# M239X.net
KiCad netlist of a schematic drawn in EAGLE
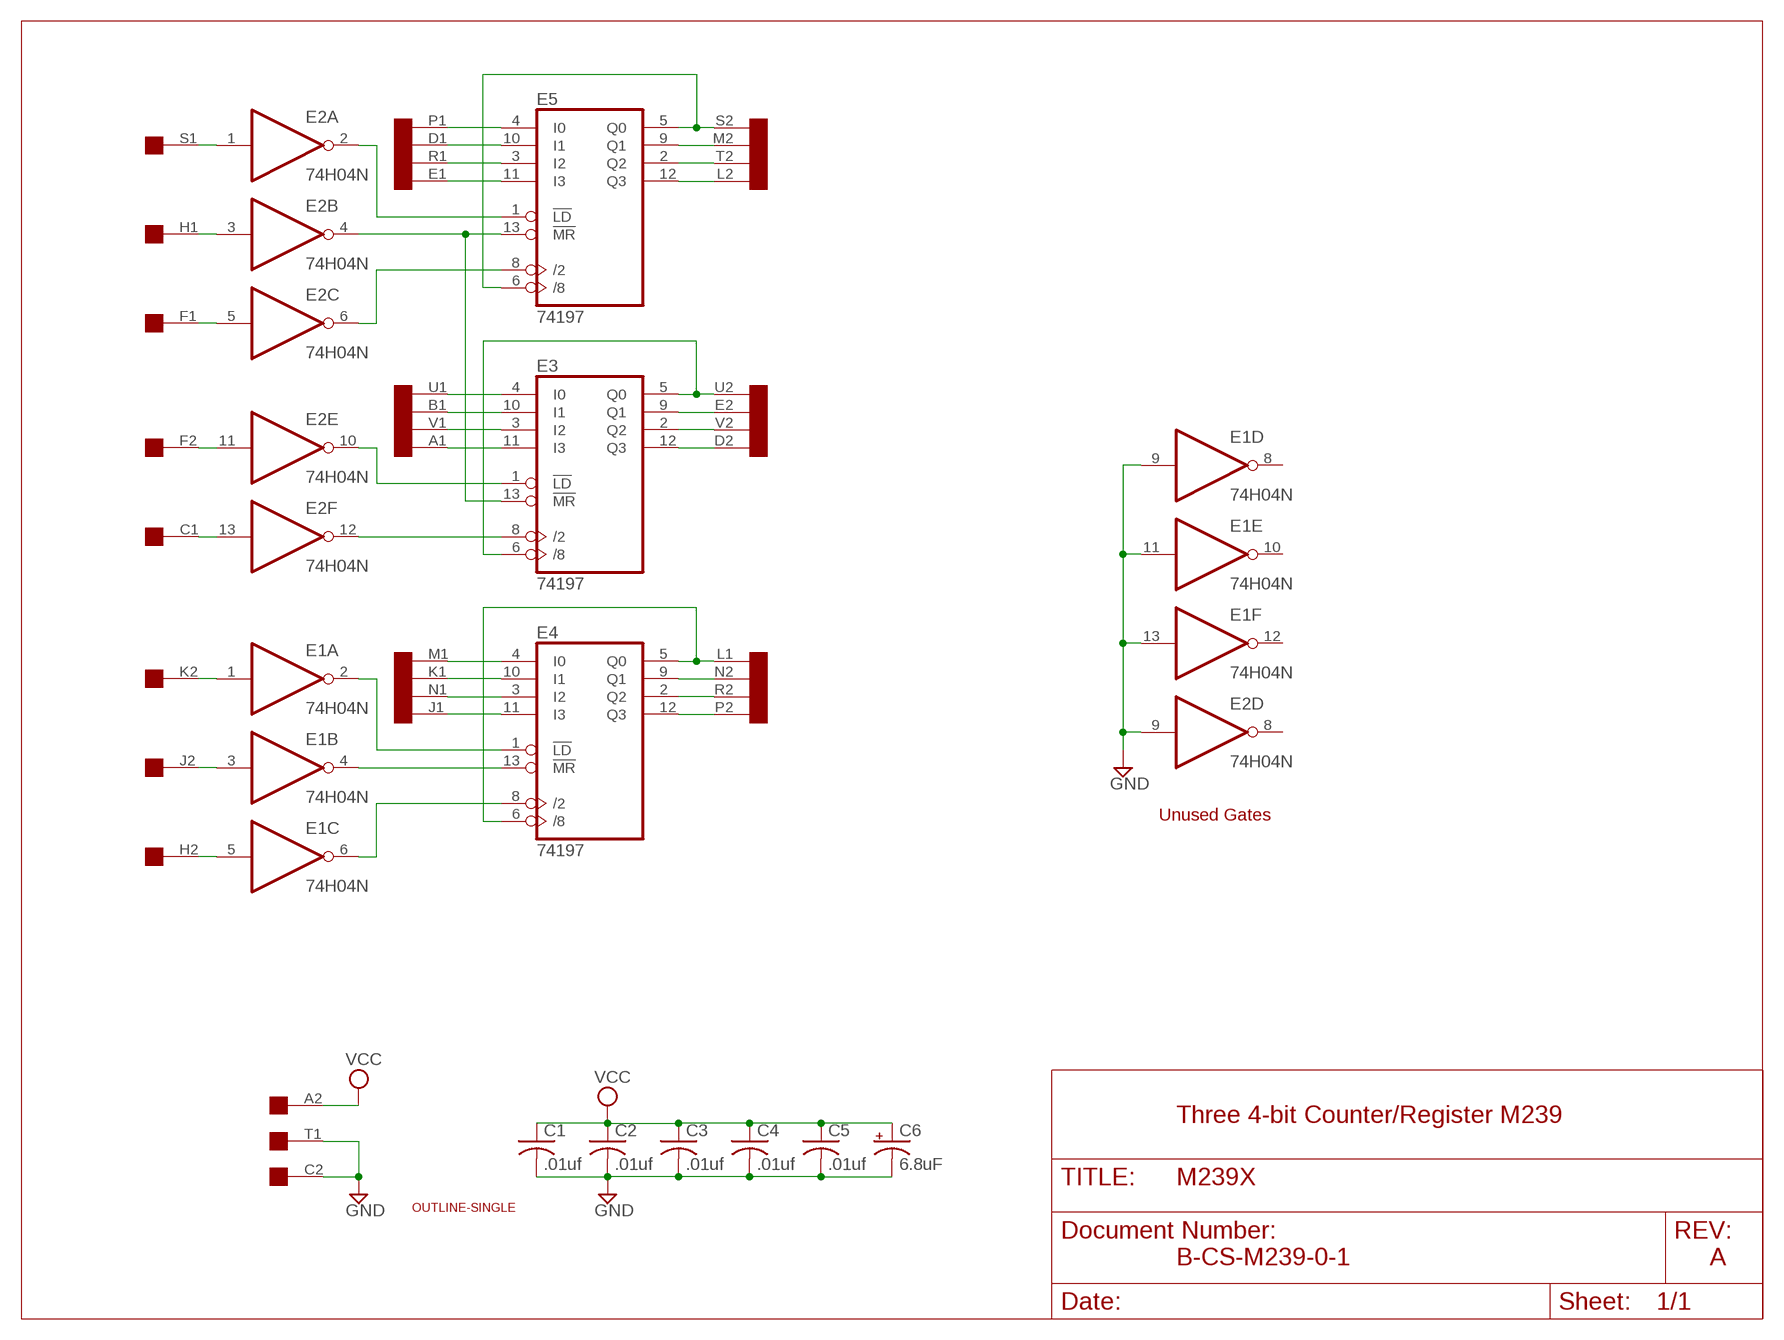
[diagram p0: schematic, sheet 1]

(export (version "E")
  (design (tool "Eeschema 10.0.6"))
  (components
    (comp (ref "C1")
      (value ".01uf")
      (footprint "eagle-import:C050-025X075")
      (libsource (lib "eagle-import") (part "C-US050-025X075"))
    )
    (comp (ref "C2")
      (value ".01uf")
      (footprint "eagle-import:C050-025X075")
      (libsource (lib "eagle-import") (part "C-US050-025X075"))
    )
    (comp (ref "C3")
      (value ".01uf")
      (footprint "eagle-import:C050-025X075")
      (libsource (lib "eagle-import") (part "C-US050-025X075"))
    )
    (comp (ref "C4")
      (value ".01uf")
      (footprint "eagle-import:C050-025X075")
      (libsource (lib "eagle-import") (part "C-US050-025X075"))
    )
    (comp (ref "C5")
      (value ".01uf")
      (footprint "eagle-import:C050-025X075")
      (libsource (lib "eagle-import") (part "C-US050-025X075"))
    )
    (comp (ref "C6")
      (value "6.8uF")
      (footprint "eagle-import:E22-6")
      (libsource (lib "eagle-import") (part "CPOL-USE22-6AXIAL"))
    )
    (comp (ref "E1")
      (value "74H04N")
      (footprint "eagle-import:DIL14")
      (libsource (lib "eagle-import") (part "7404N"))
    )
    (comp (ref "E2")
      (value "74H04N")
      (footprint "eagle-import:DIL14")
      (libsource (lib "eagle-import") (part "7404N"))
    )
    (comp (ref "E3")
      (value "74197")
      (footprint "eagle-import:DIL14")
      (libsource (lib "eagle-import") (part "74LS197"))
    )
    (comp (ref "E4")
      (value "74197")
      (footprint "eagle-import:DIL14")
      (libsource (lib "eagle-import") (part "74LS197"))
    )
    (comp (ref "E5")
      (value "74197")
      (footprint "eagle-import:DIL14")
      (libsource (lib "eagle-import") (part "74LS197"))
    )
    (comp (ref "U$1")
      (value "OUTLINE-SINGLE")
      (footprint "eagle-import:SINGLE")
      (libsource (lib "eagle-import") (part "OUTLINE-SINGLE"))
    )
    (comp (ref "U$4")
      (value "SINGLE")
      (footprint "eagle-import:EDGE-CON2")
      (libsource (lib "eagle-import") (part "SINGLE"))
    )
  )
  (nets
    (net (code "1") (name "GND") (class "Default")
      (node (ref "C1") (pin "2") (pinfunction "2_2") (pintype "passive"))
      (node (ref "C2") (pin "2") (pinfunction "2_2") (pintype "passive"))
      (node (ref "C3") (pin "2") (pinfunction "2_2") (pintype "passive"))
      (node (ref "C4") (pin "2") (pinfunction "2_2") (pintype "passive"))
      (node (ref "C5") (pin "2") (pinfunction "2_2") (pintype "passive"))
      (node (ref "C6") (pin "-") (pinfunction "-_-") (pintype "passive"))
      (node (ref "E1") (pin "11") (pinfunction "I_11") (pintype "input"))
      (node (ref "E1") (pin "13") (pinfunction "I_13") (pintype "input"))
      (node (ref "E1") (pin "9") (pinfunction "I_9") (pintype "input"))
      (node (ref "E2") (pin "9") (pinfunction "I_9") (pintype "input"))
      (node (ref "U$4") (pin "C2") (pinfunction "1_C2") (pintype "bidirectional"))
      (node (ref "U$4") (pin "T1") (pinfunction "1_T1") (pintype "bidirectional"))
    )
    (net (code "2") (name "Net-(E1A-I)") (class "Default")
      (node (ref "E1") (pin "1") (pinfunction "I_1") (pintype "input"))
      (node (ref "U$4") (pin "K2") (pinfunction "1_K2") (pintype "bidirectional"))
    )
    (net (code "3") (name "Net-(E1A-O)") (class "Default")
      (node (ref "E1") (pin "2") (pinfunction "O_2") (pintype "output"))
      (node (ref "E4") (pin "1") (pinfunction "~{LD}_1") (pintype "input"))
    )
    (net (code "4") (name "Net-(E1B-I)") (class "Default")
      (node (ref "E1") (pin "3") (pinfunction "I_3") (pintype "input"))
      (node (ref "U$4") (pin "J2") (pinfunction "1_J2") (pintype "bidirectional"))
    )
    (net (code "5") (name "Net-(E1B-O)") (class "Default")
      (node (ref "E1") (pin "4") (pinfunction "O_4") (pintype "output"))
      (node (ref "E4") (pin "13") (pinfunction "~{MR}_13") (pintype "input"))
    )
    (net (code "6") (name "Net-(E1C-I)") (class "Default")
      (node (ref "E1") (pin "5") (pinfunction "I_5") (pintype "input"))
      (node (ref "U$4") (pin "H2") (pinfunction "1_H2") (pintype "bidirectional"))
    )
    (net (code "7") (name "Net-(E1C-O)") (class "Default")
      (node (ref "E1") (pin "6") (pinfunction "O_6") (pintype "output"))
      (node (ref "E4") (pin "8") (pinfunction "/2_8") (pintype "bidirectional"))
    )
    (net (code "8") (name "Net-(E2A-I)") (class "Default")
      (node (ref "E2") (pin "1") (pinfunction "I_1") (pintype "input"))
      (node (ref "U$4") (pin "S1") (pinfunction "1_S1") (pintype "bidirectional"))
    )
    (net (code "9") (name "Net-(E2A-O)") (class "Default")
      (node (ref "E2") (pin "2") (pinfunction "O_2") (pintype "output"))
      (node (ref "E5") (pin "1") (pinfunction "~{LD}_1") (pintype "input"))
    )
    (net (code "10") (name "Net-(E2B-I)") (class "Default")
      (node (ref "E2") (pin "3") (pinfunction "I_3") (pintype "input"))
      (node (ref "U$4") (pin "H1") (pinfunction "1_H1") (pintype "bidirectional"))
    )
    (net (code "11") (name "Net-(E2B-O)") (class "Default")
      (node (ref "E2") (pin "4") (pinfunction "O_4") (pintype "output"))
      (node (ref "E3") (pin "13") (pinfunction "~{MR}_13") (pintype "input"))
      (node (ref "E5") (pin "13") (pinfunction "~{MR}_13") (pintype "input"))
    )
    (net (code "12") (name "Net-(E2C-I)") (class "Default")
      (node (ref "E2") (pin "5") (pinfunction "I_5") (pintype "input"))
      (node (ref "U$4") (pin "F1") (pinfunction "1_F1") (pintype "bidirectional"))
    )
    (net (code "13") (name "Net-(E2C-O)") (class "Default")
      (node (ref "E2") (pin "6") (pinfunction "O_6") (pintype "output"))
      (node (ref "E5") (pin "8") (pinfunction "/2_8") (pintype "bidirectional"))
    )
    (net (code "14") (name "Net-(E2E-I)") (class "Default")
      (node (ref "E2") (pin "11") (pinfunction "I_11") (pintype "input"))
      (node (ref "U$4") (pin "F2") (pinfunction "1_F2") (pintype "bidirectional"))
    )
    (net (code "15") (name "Net-(E2E-O)") (class "Default")
      (node (ref "E2") (pin "10") (pinfunction "O_10") (pintype "output"))
      (node (ref "E3") (pin "1") (pinfunction "~{LD}_1") (pintype "input"))
    )
    (net (code "16") (name "Net-(E2F-I)") (class "Default")
      (node (ref "E2") (pin "13") (pinfunction "I_13") (pintype "input"))
      (node (ref "U$4") (pin "C1") (pinfunction "1_C1") (pintype "bidirectional"))
    )
    (net (code "17") (name "Net-(E2F-O)") (class "Default")
      (node (ref "E2") (pin "12") (pinfunction "O_12") (pintype "output"))
      (node (ref "E3") (pin "8") (pinfunction "/2_8") (pintype "bidirectional"))
    )
    (net (code "18") (name "Net-(E3A-I0)") (class "Default")
      (node (ref "E3") (pin "4") (pinfunction "I0_4") (pintype "input"))
      (node (ref "U$4") (pin "U1") (pinfunction "1_U1") (pintype "bidirectional"))
    )
    (net (code "19") (name "Net-(E3A-I1)") (class "Default")
      (node (ref "E3") (pin "10") (pinfunction "I1_10") (pintype "input"))
      (node (ref "U$4") (pin "B1") (pinfunction "1_B1") (pintype "bidirectional"))
    )
    (net (code "20") (name "Net-(E3A-I2)") (class "Default")
      (node (ref "E3") (pin "3") (pinfunction "I2_3") (pintype "input"))
      (node (ref "U$4") (pin "V1") (pinfunction "1_V1") (pintype "bidirectional"))
    )
    (net (code "21") (name "Net-(E3A-I3)") (class "Default")
      (node (ref "E3") (pin "11") (pinfunction "I3_11") (pintype "input"))
      (node (ref "U$4") (pin "A1") (pinfunction "1_A1") (pintype "bidirectional"))
    )
    (net (code "22") (name "Net-(E3A-Q0)") (class "Default")
      (node (ref "E3") (pin "5") (pinfunction "Q0_5") (pintype "output"))
      (node (ref "E3") (pin "6") (pinfunction "/8_6") (pintype "bidirectional"))
      (node (ref "U$4") (pin "U2") (pinfunction "1_U2") (pintype "bidirectional"))
    )
    (net (code "23") (name "Net-(E3A-Q1)") (class "Default")
      (node (ref "E3") (pin "9") (pinfunction "Q1_9") (pintype "output"))
      (node (ref "U$4") (pin "E2") (pinfunction "1_E2") (pintype "bidirectional"))
    )
    (net (code "24") (name "Net-(E3A-Q2)") (class "Default")
      (node (ref "E3") (pin "2") (pinfunction "Q2_2") (pintype "output"))
      (node (ref "U$4") (pin "V2") (pinfunction "1_V2") (pintype "bidirectional"))
    )
    (net (code "25") (name "Net-(E3A-Q3)") (class "Default")
      (node (ref "E3") (pin "12") (pinfunction "Q3_12") (pintype "output"))
      (node (ref "U$4") (pin "D2") (pinfunction "1_D2") (pintype "bidirectional"))
    )
    (net (code "26") (name "Net-(E4A-I0)") (class "Default")
      (node (ref "E4") (pin "4") (pinfunction "I0_4") (pintype "input"))
      (node (ref "U$4") (pin "M1") (pinfunction "1_M1") (pintype "bidirectional"))
    )
    (net (code "27") (name "Net-(E4A-I1)") (class "Default")
      (node (ref "E4") (pin "10") (pinfunction "I1_10") (pintype "input"))
      (node (ref "U$4") (pin "K1") (pinfunction "1_K1") (pintype "bidirectional"))
    )
    (net (code "28") (name "Net-(E4A-I2)") (class "Default")
      (node (ref "E4") (pin "3") (pinfunction "I2_3") (pintype "input"))
      (node (ref "U$4") (pin "N1") (pinfunction "1_N1") (pintype "bidirectional"))
    )
    (net (code "29") (name "Net-(E4A-I3)") (class "Default")
      (node (ref "E4") (pin "11") (pinfunction "I3_11") (pintype "input"))
      (node (ref "U$4") (pin "J1") (pinfunction "1_J1") (pintype "bidirectional"))
    )
    (net (code "30") (name "Net-(E4A-Q0)") (class "Default")
      (node (ref "E4") (pin "5") (pinfunction "Q0_5") (pintype "output"))
      (node (ref "E4") (pin "6") (pinfunction "/8_6") (pintype "bidirectional"))
      (node (ref "U$4") (pin "L1") (pinfunction "1_L1") (pintype "bidirectional"))
    )
    (net (code "31") (name "Net-(E4A-Q1)") (class "Default")
      (node (ref "E4") (pin "9") (pinfunction "Q1_9") (pintype "output"))
      (node (ref "U$4") (pin "N2") (pinfunction "1_N2") (pintype "bidirectional"))
    )
    (net (code "32") (name "Net-(E4A-Q2)") (class "Default")
      (node (ref "E4") (pin "2") (pinfunction "Q2_2") (pintype "output"))
      (node (ref "U$4") (pin "R2") (pinfunction "1_R2") (pintype "bidirectional"))
    )
    (net (code "33") (name "Net-(E4A-Q3)") (class "Default")
      (node (ref "E4") (pin "12") (pinfunction "Q3_12") (pintype "output"))
      (node (ref "U$4") (pin "P2") (pinfunction "1_P2") (pintype "bidirectional"))
    )
    (net (code "34") (name "Net-(E5A-I0)") (class "Default")
      (node (ref "E5") (pin "4") (pinfunction "I0_4") (pintype "input"))
      (node (ref "U$4") (pin "P1") (pinfunction "1_P1") (pintype "bidirectional"))
    )
    (net (code "35") (name "Net-(E5A-I1)") (class "Default")
      (node (ref "E5") (pin "10") (pinfunction "I1_10") (pintype "input"))
      (node (ref "U$4") (pin "D1") (pinfunction "1_D1") (pintype "bidirectional"))
    )
    (net (code "36") (name "Net-(E5A-I2)") (class "Default")
      (node (ref "E5") (pin "3") (pinfunction "I2_3") (pintype "input"))
      (node (ref "U$4") (pin "R1") (pinfunction "1_R1") (pintype "bidirectional"))
    )
    (net (code "37") (name "Net-(E5A-I3)") (class "Default")
      (node (ref "E5") (pin "11") (pinfunction "I3_11") (pintype "input"))
      (node (ref "U$4") (pin "E1") (pinfunction "1_E1") (pintype "bidirectional"))
    )
    (net (code "38") (name "Net-(E5A-Q0)") (class "Default")
      (node (ref "E5") (pin "5") (pinfunction "Q0_5") (pintype "output"))
      (node (ref "E5") (pin "6") (pinfunction "/8_6") (pintype "bidirectional"))
      (node (ref "U$4") (pin "S2") (pinfunction "1_S2") (pintype "bidirectional"))
    )
    (net (code "39") (name "Net-(E5A-Q1)") (class "Default")
      (node (ref "E5") (pin "9") (pinfunction "Q1_9") (pintype "output"))
      (node (ref "U$4") (pin "M2") (pinfunction "1_M2") (pintype "bidirectional"))
    )
    (net (code "40") (name "Net-(E5A-Q2)") (class "Default")
      (node (ref "E5") (pin "2") (pinfunction "Q2_2") (pintype "output"))
      (node (ref "U$4") (pin "T2") (pinfunction "1_T2") (pintype "bidirectional"))
    )
    (net (code "41") (name "Net-(E5A-Q3)") (class "Default")
      (node (ref "E5") (pin "12") (pinfunction "Q3_12") (pintype "output"))
      (node (ref "U$4") (pin "L2") (pinfunction "1_L2") (pintype "bidirectional"))
    )
    (net (code "42") (name "VCC") (class "Default")
      (node (ref "C1") (pin "1") (pinfunction "1_1") (pintype "passive"))
      (node (ref "C2") (pin "1") (pinfunction "1_1") (pintype "passive"))
      (node (ref "C3") (pin "1") (pinfunction "1_1") (pintype "passive"))
      (node (ref "C4") (pin "1") (pinfunction "1_1") (pintype "passive"))
      (node (ref "C5") (pin "1") (pinfunction "1_1") (pintype "passive"))
      (node (ref "C6") (pin "+") (pinfunction "+_+") (pintype "passive"))
      (node (ref "U$4") (pin "A2") (pinfunction "1_A2") (pintype "bidirectional"))
    )
    (net (code "43") (name "unconnected-(E1D-O-Pad8)") (class "Default")
      (node (ref "E1") (pin "8") (pinfunction "O_8") (pintype "output"))
    )
    (net (code "44") (name "unconnected-(E1E-O-Pad10)") (class "Default")
      (node (ref "E1") (pin "10") (pinfunction "O_10") (pintype "output"))
    )
    (net (code "45") (name "unconnected-(E1F-O-Pad12)") (class "Default")
      (node (ref "E1") (pin "12") (pinfunction "O_12") (pintype "output"))
    )
    (net (code "46") (name "unconnected-(E2D-O-Pad8)") (class "Default")
      (node (ref "E2") (pin "8") (pinfunction "O_8") (pintype "output"))
    )
  )
)
